# MAGI_sCM0Core.net
KiCad netlist of a schematic drawn in Altium Designer
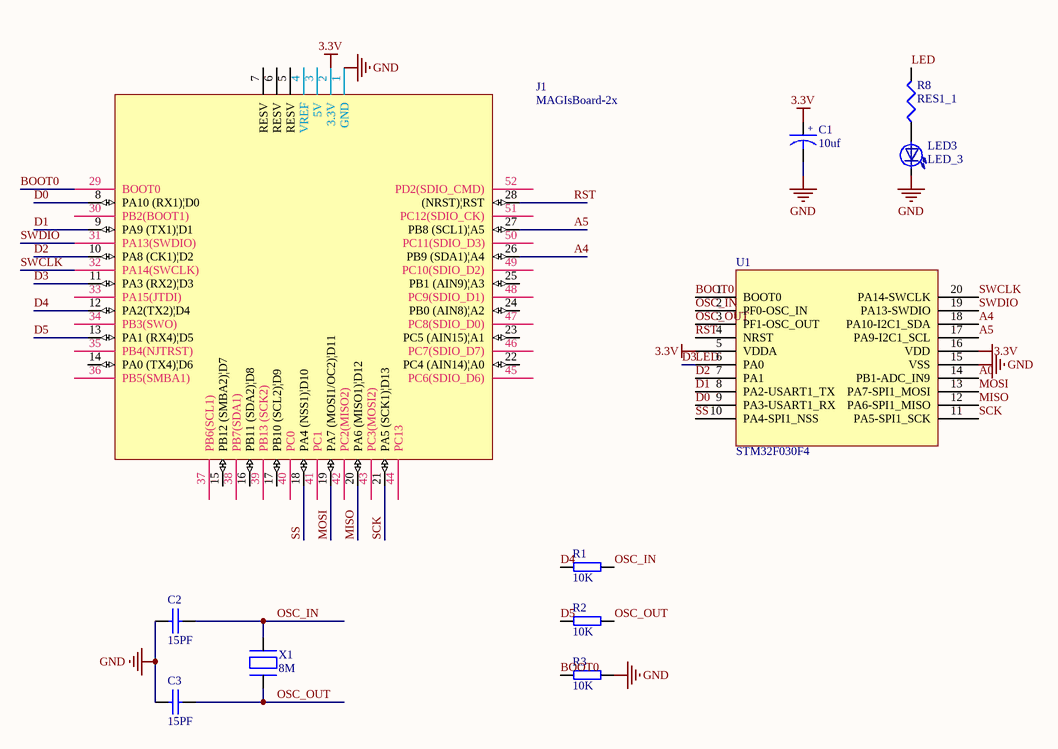
[diagram p0: MAGI'sCM0Core.SchDoc]

(export (version "E")
  (design (tool "Eeschema 10.0.6"))
  (components
    (comp (ref "C1")
      (value "10uf")
      (footprint "6-0805_n")
      (description "Capacitor")
      (libsource (lib "电容器") (part "CAPACITOR POL"))
    )
    (comp (ref "C2") (value "15PF") (footprint "6-0805_n") (libsource (lib "STM32") (part "CAP")))
    (comp (ref "C3") (value "15PF") (footprint "6-0805_n") (libsource (lib "STM32") (part "CAP")))
    (comp (ref "J1")
      (value "MAGIsBoard-2x")
      (footprint "MAGIsBoard-2x")
      (libsource (lib "MAGIsBoard") (part "MAGIsBoard-2x"))
    )
    (comp (ref "LED3") (value "LED_3") (footprint "6-0805_N") (libsource (lib "二极管") (part "LED_3")))
    (comp (ref "R1") (value "10K") (footprint "6-0805_n") (libsource (lib "STM32") (part "RES")))
    (comp (ref "R2") (value "10K") (footprint "6-0805_n") (libsource (lib "STM32") (part "RES")))
    (comp (ref "R3") (value "10K") (footprint "6-0805_n") (libsource (lib "STM32") (part "RES")))
    (comp (ref "R8") (value "RES1_1") (footprint "6-0805_N") (libsource (lib "电阻器") (part "RES1_1")))
    (comp (ref "U1")
      (value "STM32F030F4")
      (footprint "STM32F030")
      (libsource (lib "MCU") (part "STM32F030F4"))
    )
    (comp (ref "X1") (value "8M") (footprint "5032") (libsource (lib "STM32") (part "CRYSTAL")))
  )
  (nets
    (net (code "1") (name "/A0") (class "Default")
      (node (ref "U1") (pin "14") (pinfunction "PB1-ADC_IN9_14") (pintype "passive"))
    )
    (net (code "2") (name "/A4") (class "Default")
      (node (ref "J1") (pin "26") (pinfunction "PB9_(SDA1)¦A4_26") (pintype "bidirectional"))
      (node (ref "U1") (pin "18") (pinfunction "PA10-I2C1_SDA_18") (pintype "passive"))
    )
    (net (code "3") (name "/A5") (class "Default")
      (node (ref "J1") (pin "27") (pinfunction "PB8_(SCL1)¦A5_27") (pintype "bidirectional"))
      (node (ref "U1") (pin "17") (pinfunction "PA9-I2C1_SCL_17") (pintype "passive"))
    )
    (net (code "4") (name "/BOOT0") (class "Default")
      (node (ref "J1") (pin "29") (pinfunction "BOOT0_29") (pintype "passive"))
      (node (ref "R3") (pin "2") (pinfunction "2_2") (pintype "passive"))
      (node (ref "U1") (pin "1") (pinfunction "BOOT0_1") (pintype "passive"))
    )
    (net (code "5") (name "/D0") (class "Default")
      (node (ref "J1") (pin "8") (pinfunction "PA10_(RX1)¦D0_8") (pintype "bidirectional"))
      (node (ref "U1") (pin "9") (pinfunction "PA3-USART1_RX_9") (pintype "passive"))
    )
    (net (code "6") (name "/D1") (class "Default")
      (node (ref "J1") (pin "9") (pinfunction "PA9_(TX1)¦D1_9") (pintype "bidirectional"))
      (node (ref "U1") (pin "8") (pinfunction "PA2-USART1_TX_8") (pintype "passive"))
    )
    (net (code "7") (name "/D2") (class "Default")
      (node (ref "J1") (pin "10") (pinfunction "PA8_(CK1)¦D2_10") (pintype "bidirectional"))
      (node (ref "U1") (pin "7") (pinfunction "PA1_7") (pintype "passive"))
    )
    (net (code "8") (name "/D3") (class "Default")
      (node (ref "J1") (pin "11") (pinfunction "PA3_(RX2)¦D3_11") (pintype "bidirectional"))
      (node (ref "R8") (pin "2") (pinfunction "2_2") (pintype "passive"))
      (node (ref "U1") (pin "6") (pinfunction "PA0_6") (pintype "passive"))
    )
    (net (code "9") (name "/D4") (class "Default")
      (node (ref "J1") (pin "12") (pinfunction "PA2(TX2)¦D4_12") (pintype "bidirectional"))
      (node (ref "R1") (pin "2") (pinfunction "2_2") (pintype "passive"))
    )
    (net (code "10") (name "/D5") (class "Default")
      (node (ref "J1") (pin "13") (pinfunction "PA1_(RX4)¦D5_13") (pintype "bidirectional"))
      (node (ref "R2") (pin "2") (pinfunction "2_2") (pintype "passive"))
    )
    (net (code "11") (name "/MISO") (class "Default")
      (node (ref "J1") (pin "20") (pinfunction "PA6_(MISO1)¦D12_20") (pintype "bidirectional"))
      (node (ref "U1") (pin "12") (pinfunction "PA6-SPI1_MISO_12") (pintype "passive"))
    )
    (net (code "12") (name "/MOSI") (class "Default")
      (node (ref "J1") (pin "19") (pinfunction "PA7_(MOSI1/OC2)¦D11_19") (pintype "bidirectional"))
      (node (ref "U1") (pin "13") (pinfunction "PA7-SPI1_MOSI_13") (pintype "passive"))
    )
    (net (code "13") (name "/OSC_IN") (class "Default")
      (node (ref "C2") (pin "2") (pinfunction "2_2") (pintype "passive"))
      (node (ref "R1") (pin "1") (pinfunction "1_1") (pintype "passive"))
      (node (ref "U1") (pin "2") (pinfunction "PF0-OSC_IN_2") (pintype "passive"))
      (node (ref "X1") (pin "1") (pinfunction "1_1") (pintype "passive"))
    )
    (net (code "14") (name "/OSC_OUT") (class "Default")
      (node (ref "C3") (pin "2") (pinfunction "2_2") (pintype "passive"))
      (node (ref "R2") (pin "1") (pinfunction "1_1") (pintype "passive"))
      (node (ref "U1") (pin "3") (pinfunction "PF1-OSC_OUT_3") (pintype "passive"))
      (node (ref "X1") (pin "2") (pinfunction "2_2") (pintype "passive"))
    )
    (net (code "15") (name "/RST") (class "Default")
      (node (ref "J1") (pin "28") (pinfunction "(NRST)¦RST_28") (pintype "bidirectional"))
      (node (ref "U1") (pin "4") (pinfunction "NRST_4") (pintype "passive"))
    )
    (net (code "16") (name "/SCK") (class "Default")
      (node (ref "J1") (pin "21") (pinfunction "PA5_(SCK1)¦D13_21") (pintype "bidirectional"))
      (node (ref "U1") (pin "11") (pinfunction "PA5-SPI1_SCK_11") (pintype "passive"))
    )
    (net (code "17") (name "/SS") (class "Default")
      (node (ref "J1") (pin "18") (pinfunction "PA4_(NSS1)¦D10_18") (pintype "bidirectional"))
      (node (ref "U1") (pin "10") (pinfunction "PA4-SPI1_NSS_10") (pintype "passive"))
    )
    (net (code "18") (name "/SWCLK") (class "Default")
      (node (ref "J1") (pin "32") (pinfunction "PA14(SWCLK)_32") (pintype "passive"))
      (node (ref "U1") (pin "20") (pinfunction "PA14-SWCLK_20") (pintype "passive"))
    )
    (net (code "19") (name "/SWDIO") (class "Default")
      (node (ref "J1") (pin "31") (pinfunction "PA13(SWDIO)_31") (pintype "passive"))
      (node (ref "U1") (pin "19") (pinfunction "PA13-SWDIO_19") (pintype "passive"))
    )
    (net (code "20") (name "3.3V") (class "Default")
      (node (ref "C1") (pin "1") (pinfunction "1_1") (pintype "passive"))
      (node (ref "J1") (pin "2") (pinfunction "3.3V_2") (pintype "power_in"))
      (node (ref "U1") (pin "16") (pinfunction "VDD_16") (pintype "passive"))
      (node (ref "U1") (pin "5") (pinfunction "VDDA_5") (pintype "passive"))
    )
    (net (code "21") (name "GND") (class "Default")
      (node (ref "C1") (pin "2") (pinfunction "2_2") (pintype "passive"))
      (node (ref "C2") (pin "1") (pinfunction "1_1") (pintype "passive"))
      (node (ref "C3") (pin "1") (pinfunction "1_1") (pintype "passive"))
      (node (ref "J1") (pin "1") (pinfunction "GND_1") (pintype "power_in"))
      (node (ref "LED3") (pin "2") (pinfunction "K_2") (pintype "passive"))
      (node (ref "R3") (pin "1") (pinfunction "1_1") (pintype "passive"))
      (node (ref "U1") (pin "15") (pinfunction "VSS_15") (pintype "passive"))
    )
    (net (code "22") (name "Net-(LED3-A)") (class "Default")
      (node (ref "LED3") (pin "1") (pinfunction "A_1") (pintype "passive"))
      (node (ref "R8") (pin "1") (pinfunction "1_1") (pintype "passive"))
    )
    (net (code "23") (name "unconnected-(J1-5V-Pad3)") (class "Default")
      (node (ref "J1") (pin "3") (pinfunction "5V_3") (pintype "power_in"))
    )
    (net (code "24") (name "unconnected-(J1-PA0_(TX4)¦D6-Pad14)") (class "Default")
      (node (ref "J1") (pin "14") (pinfunction "PA0_(TX4)¦D6_14") (pintype "bidirectional"))
    )
    (net (code "25") (name "unconnected-(J1-PA15(JTDI)-Pad33)") (class "Default")
      (node (ref "J1") (pin "33") (pinfunction "PA15(JTDI)_33") (pintype "passive"))
    )
    (net (code "26") (name "unconnected-(J1-PB0_(AIN8)¦A2-Pad24)") (class "Default")
      (node (ref "J1") (pin "24") (pinfunction "PB0_(AIN8)¦A2_24") (pintype "bidirectional"))
    )
    (net (code "27") (name "unconnected-(J1-PB1_(AIN9)¦A3-Pad25)") (class "Default")
      (node (ref "J1") (pin "25") (pinfunction "PB1_(AIN9)¦A3_25") (pintype "bidirectional"))
    )
    (net (code "28") (name "unconnected-(J1-PB2(BOOT1)-Pad30)") (class "Default")
      (node (ref "J1") (pin "30") (pinfunction "PB2(BOOT1)_30") (pintype "passive"))
    )
    (net (code "29") (name "unconnected-(J1-PB3(SWO)-Pad34)") (class "Default")
      (node (ref "J1") (pin "34") (pinfunction "PB3(SWO)_34") (pintype "passive"))
    )
    (net (code "30") (name "unconnected-(J1-PB4(NJTRST)-Pad35)") (class "Default")
      (node (ref "J1") (pin "35") (pinfunction "PB4(NJTRST)_35") (pintype "passive"))
    )
    (net (code "31") (name "unconnected-(J1-PB5(SMBA1)-Pad36)") (class "Default")
      (node (ref "J1") (pin "36") (pinfunction "PB5(SMBA1)_36") (pintype "passive"))
    )
    (net (code "32") (name "unconnected-(J1-PB6(SCL1)-Pad37)") (class "Default")
      (node (ref "J1") (pin "37") (pinfunction "PB6(SCL1)_37") (pintype "passive"))
    )
    (net (code "33") (name "unconnected-(J1-PB7(SDA1)-Pad38)") (class "Default")
      (node (ref "J1") (pin "38") (pinfunction "PB7(SDA1)_38") (pintype "passive"))
    )
    (net (code "34") (name "unconnected-(J1-PB10_(SCL2)¦D9-Pad17)") (class "Default")
      (node (ref "J1") (pin "17") (pinfunction "PB10_(SCL2)¦D9_17") (pintype "bidirectional"))
    )
    (net (code "35") (name "unconnected-(J1-PB11_(SDA2)¦D8-Pad16)") (class "Default")
      (node (ref "J1") (pin "16") (pinfunction "PB11_(SDA2)¦D8_16") (pintype "bidirectional"))
    )
    (net (code "36") (name "unconnected-(J1-PB12_(SMBA2)¦D7-Pad15)") (class "Default")
      (node (ref "J1") (pin "15") (pinfunction "PB12_(SMBA2)¦D7_15") (pintype "bidirectional"))
    )
    (net (code "37") (name "unconnected-(J1-PB13_(SCK2)-Pad39)") (class "Default")
      (node (ref "J1") (pin "39") (pinfunction "PB13_(SCK2)_39") (pintype "passive"))
    )
    (net (code "38") (name "unconnected-(J1-PC0-Pad40)") (class "Default")
      (node (ref "J1") (pin "40") (pinfunction "PC0_40") (pintype "passive"))
    )
    (net (code "39") (name "unconnected-(J1-PC1-Pad41)") (class "Default")
      (node (ref "J1") (pin "41") (pinfunction "PC1_41") (pintype "passive"))
    )
    (net (code "40") (name "unconnected-(J1-PC2(MISO2)-Pad42)") (class "Default")
      (node (ref "J1") (pin "42") (pinfunction "PC2(MISO2)_42") (pintype "passive"))
    )
    (net (code "41") (name "unconnected-(J1-PC3(MOSI2)-Pad43)") (class "Default")
      (node (ref "J1") (pin "43") (pinfunction "PC3(MOSI2)_43") (pintype "passive"))
    )
    (net (code "42") (name "unconnected-(J1-PC4_(AIN14)¦A0-Pad22)") (class "Default")
      (node (ref "J1") (pin "22") (pinfunction "PC4_(AIN14)¦A0_22") (pintype "bidirectional"))
    )
    (net (code "43") (name "unconnected-(J1-PC5_(AIN15)¦A1-Pad23)") (class "Default")
      (node (ref "J1") (pin "23") (pinfunction "PC5_(AIN15)¦A1_23") (pintype "bidirectional"))
    )
    (net (code "44") (name "unconnected-(J1-PC6(SDIO_D6)-Pad45)") (class "Default")
      (node (ref "J1") (pin "45") (pinfunction "PC6(SDIO_D6)_45") (pintype "passive"))
    )
    (net (code "45") (name "unconnected-(J1-PC7(SDIO_D7)-Pad46)") (class "Default")
      (node (ref "J1") (pin "46") (pinfunction "PC7(SDIO_D7)_46") (pintype "passive"))
    )
    (net (code "46") (name "unconnected-(J1-PC8(SDIO_D0)-Pad47)") (class "Default")
      (node (ref "J1") (pin "47") (pinfunction "PC8(SDIO_D0)_47") (pintype "passive"))
    )
    (net (code "47") (name "unconnected-(J1-PC9(SDIO_D1)-Pad48)") (class "Default")
      (node (ref "J1") (pin "48") (pinfunction "PC9(SDIO_D1)_48") (pintype "passive"))
    )
    (net (code "48") (name "unconnected-(J1-PC10(SDIO_D2)-Pad49)") (class "Default")
      (node (ref "J1") (pin "49") (pinfunction "PC10(SDIO_D2)_49") (pintype "passive"))
    )
    (net (code "49") (name "unconnected-(J1-PC11(SDIO_D3)-Pad50)") (class "Default")
      (node (ref "J1") (pin "50") (pinfunction "PC11(SDIO_D3)_50") (pintype "passive"))
    )
    (net (code "50") (name "unconnected-(J1-PC12(SDIO_CK)-Pad51)") (class "Default")
      (node (ref "J1") (pin "51") (pinfunction "PC12(SDIO_CK)_51") (pintype "passive"))
    )
    (net (code "51") (name "unconnected-(J1-PC13-Pad44)") (class "Default")
      (node (ref "J1") (pin "44") (pinfunction "PC13_44") (pintype "passive"))
    )
    (net (code "52") (name "unconnected-(J1-PD2(SDIO_CMD)-Pad52)") (class "Default")
      (node (ref "J1") (pin "52") (pinfunction "PD2(SDIO_CMD)_52") (pintype "passive"))
    )
    (net (code "53") (name "unconnected-(J1-RESV-Pad5)") (class "Default")
      (node (ref "J1") (pin "5") (pinfunction "RESV_5") (pintype "passive"))
    )
    (net (code "54") (name "unconnected-(J1-RESV-Pad6)") (class "Default")
      (node (ref "J1") (pin "6") (pinfunction "RESV_6") (pintype "passive"))
    )
    (net (code "55") (name "unconnected-(J1-RESV-Pad7)") (class "Default")
      (node (ref "J1") (pin "7") (pinfunction "RESV_7") (pintype "passive"))
    )
    (net (code "56") (name "unconnected-(J1-VREF-Pad4)") (class "Default")
      (node (ref "J1") (pin "4") (pinfunction "VREF_4") (pintype "passive"))
    )
  )
)
